# BootLoader.net
KiCad netlist of a schematic drawn in EAGLE
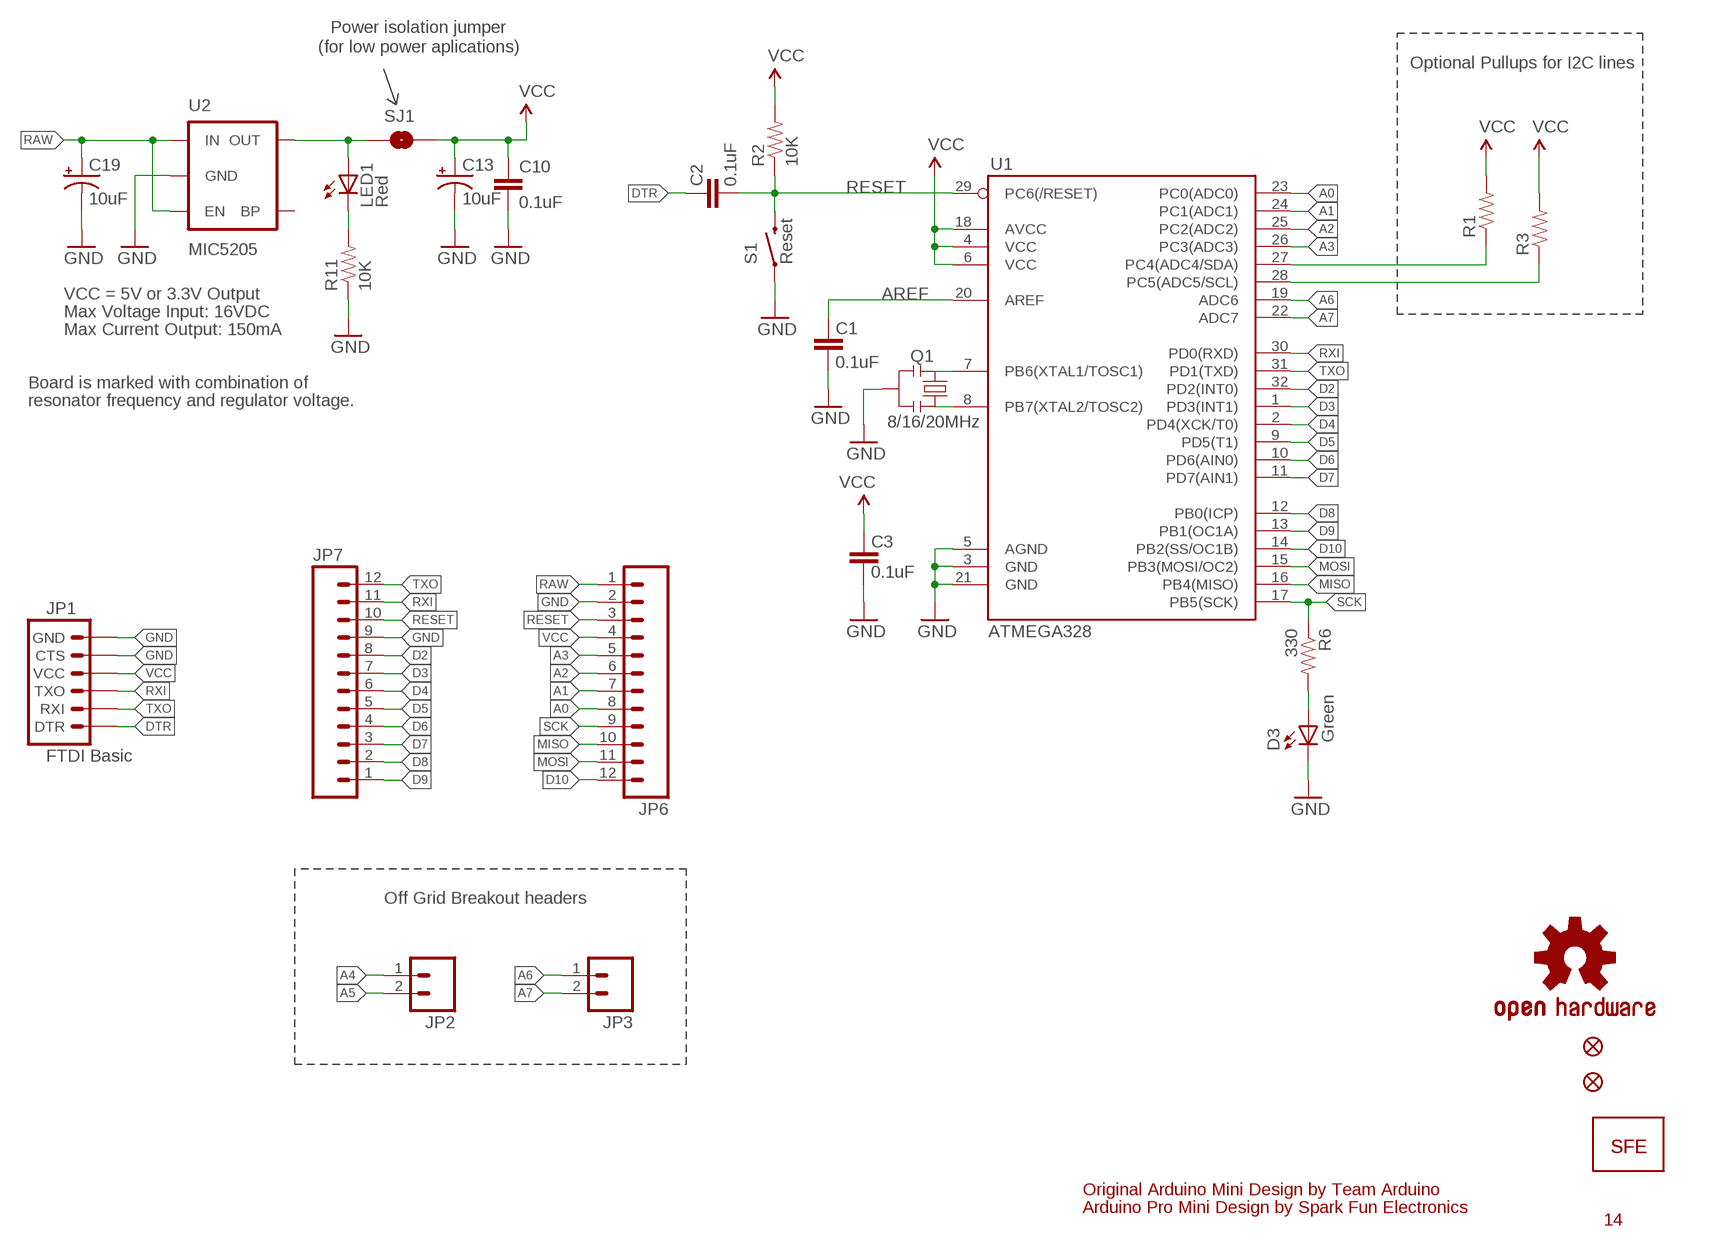
[diagram p0: schematic, sheet 1]

(export (version "E")
  (design (tool "Eeschema 10.0.6"))
  (components
    (comp (ref "C1")
      (value "0.1uF")
      (footprint "eagle-import:0603-CAP")
      (libsource (lib "eagle-import") (part "CAP0603-CAP"))
    )
    (comp (ref "C2")
      (value "0.1uF")
      (footprint "eagle-import:0603-CAP")
      (libsource (lib "eagle-import") (part "CAP0603-CAP"))
    )
    (comp (ref "C3")
      (value "0.1uF")
      (footprint "eagle-import:0603-CAP")
      (libsource (lib "eagle-import") (part "CAP0603-CAP"))
    )
    (comp (ref "C10")
      (value "0.1uF")
      (footprint "eagle-import:0603-CAP")
      (libsource (lib "eagle-import") (part "CAP0603-CAP"))
    )
    (comp (ref "C13")
      (value "10uF")
      (footprint "eagle-import:EIA3216")
      (libsource (lib "eagle-import") (part "CAP_POL1206"))
    )
    (comp (ref "C19")
      (value "10uF")
      (footprint "eagle-import:EIA3216")
      (libsource (lib "eagle-import") (part "CAP_POL1206"))
    )
    (comp (ref "D3")
      (value "Green")
      (footprint "eagle-import:0603-LED-ALT1")
      (libsource (lib "eagle-import") (part "LED"))
    )
    (comp (ref "JP1")
      (value "FTDI Basic")
      (footprint "eagle-import:1X06")
      (libsource (lib "eagle-import") (part "ARDUINO_SERIAL_PROGRAMPTH"))
    )
    (comp (ref "JP2")
      (value "M02PTH")
      (footprint "eagle-import:1X02")
      (libsource (lib "eagle-import") (part "M02PTH"))
    )
    (comp (ref "JP3")
      (value "M02PTH")
      (footprint "eagle-import:1X02")
      (libsource (lib "eagle-import") (part "M02PTH"))
    )
    (comp (ref "JP5")
      (value "FIDUCIALUFIDUCIAL")
      (footprint "eagle-import:MICRO-FIDUCIAL")
      (libsource (lib "eagle-import") (part "FIDUCIALUFIDUCIAL"))
    )
    (comp (ref "JP6")
      (value "M12PTH")
      (footprint "eagle-import:1X12")
      (libsource (lib "eagle-import") (part "M12PTH"))
    )
    (comp (ref "JP7")
      (value "M12PTH")
      (footprint "eagle-import:1X12")
      (libsource (lib "eagle-import") (part "M12PTH"))
    )
    (comp (ref "JP8")
      (value "FIDUCIALUFIDUCIAL")
      (footprint "eagle-import:MICRO-FIDUCIAL")
      (libsource (lib "eagle-import") (part "FIDUCIALUFIDUCIAL"))
    )
    (comp (ref "LED1")
      (value "Red")
      (footprint "eagle-import:0603-LED-ALT1")
      (libsource (lib "eagle-import") (part "LED"))
    )
    (comp (ref "Q1")
      (value "8/16/20MHz")
      (footprint "eagle-import:RESONATOR-SMD-1_1")
      (libsource (lib "eagle-import") (part "RESONATOR1{colon}1"))
    )
    (comp (ref "R1")
      (value "RESISTOR0603-RES")
      (footprint "eagle-import:0603-RES")
      (libsource (lib "eagle-import") (part "RESISTOR0603-RES"))
    )
    (comp (ref "R2")
      (value "10K")
      (footprint "eagle-import:0603-RES")
      (libsource (lib "eagle-import") (part "RESISTOR0603-RES"))
    )
    (comp (ref "R3")
      (value "RESISTOR0603-RES")
      (footprint "eagle-import:0603-RES")
      (libsource (lib "eagle-import") (part "RESISTOR0603-RES"))
    )
    (comp (ref "R6")
      (value "330")
      (footprint "eagle-import:0603-RES")
      (libsource (lib "eagle-import") (part "RESISTOR0603-RES"))
    )
    (comp (ref "R11")
      (value "10K")
      (footprint "eagle-import:0603-RES")
      (libsource (lib "eagle-import") (part "RESISTOR0603-RES"))
    )
    (comp (ref "S1")
      (value "Reset")
      (footprint "eagle-import:TACTILE-SWITCH-SMD-ALT01")
      (libsource (lib "eagle-import") (part "SWITCH-MOMENTARY-2SMD-ALT01"))
    )
    (comp (ref "SJ1")
      (value "SOLDERJUMPERNC")
      (footprint "eagle-import:SJ_2S")
      (libsource (lib "eagle-import") (part "SOLDERJUMPERNC"))
    )
    (comp (ref "U$1")
      (value "LOGO-SFESK")
      (footprint "eagle-import:SFE-LOGO-FLAME")
      (libsource (lib "eagle-import") (part "LOGO-SFESK"))
    )
    (comp (ref "U$3")
      (value "OSHW-LOGOS")
      (footprint "eagle-import:OSHW-LOGO-S")
      (libsource (lib "eagle-import") (part "OSHW-LOGOS"))
    )
    (comp (ref "U$11")
      (value "LOGO-SFENEW")
      (footprint "eagle-import:SFE-NEW-WEBLOGO")
      (libsource (lib "eagle-import") (part "LOGO-SFENEW"))
    )
    (comp (ref "U1")
      (value "ATMEGA328")
      (footprint "eagle-import:TQFP32-08")
      (libsource (lib "eagle-import") (part "ATMEGA168"))
    )
    (comp (ref "U2")
      (value "MIC5205")
      (footprint "eagle-import:SOT23-5")
      (libsource (lib "eagle-import") (part "V_REG_LDOSMD"))
    )
  )
  (nets
    (net (code "1") (name "/AREF") (class "Default")
      (node (ref "C1") (pin "2") (pinfunction "2_2") (pintype "passive"))
      (node (ref "U1") (pin "20") (pinfunction "AREF_20") (pintype "bidirectional"))
    )
    (net (code "2") (name "A0") (class "Default")
      (node (ref "JP6") (pin "8") (pinfunction "8_8") (pintype "passive"))
      (node (ref "U1") (pin "23") (pinfunction "PC0(ADC0)_23") (pintype "bidirectional"))
    )
    (net (code "3") (name "A1") (class "Default")
      (node (ref "JP6") (pin "7") (pinfunction "7_7") (pintype "passive"))
      (node (ref "U1") (pin "24") (pinfunction "PC1(ADC1)_24") (pintype "bidirectional"))
    )
    (net (code "4") (name "A2") (class "Default")
      (node (ref "JP6") (pin "6") (pinfunction "6_6") (pintype "passive"))
      (node (ref "U1") (pin "25") (pinfunction "PC2(ADC2)_25") (pintype "bidirectional"))
    )
    (net (code "5") (name "A3") (class "Default")
      (node (ref "JP6") (pin "5") (pinfunction "5_5") (pintype "passive"))
      (node (ref "U1") (pin "26") (pinfunction "PC3(ADC3)_26") (pintype "bidirectional"))
    )
    (net (code "6") (name "A4") (class "Default")
      (node (ref "JP2") (pin "1") (pinfunction "1_1") (pintype "passive"))
      (node (ref "R1") (pin "1") (pinfunction "1_1") (pintype "passive"))
      (node (ref "U1") (pin "27") (pinfunction "PC4(ADC4/SDA)_27") (pintype "bidirectional"))
    )
    (net (code "7") (name "A5") (class "Default")
      (node (ref "JP2") (pin "2") (pinfunction "2_2") (pintype "passive"))
      (node (ref "R3") (pin "1") (pinfunction "1_1") (pintype "passive"))
      (node (ref "U1") (pin "28") (pinfunction "PC5(ADC5/SCL)_28") (pintype "bidirectional"))
    )
    (net (code "8") (name "A6") (class "Default")
      (node (ref "JP3") (pin "1") (pinfunction "1_1") (pintype "passive"))
      (node (ref "U1") (pin "19") (pinfunction "ADC6_19") (pintype "bidirectional"))
    )
    (net (code "9") (name "A7") (class "Default")
      (node (ref "JP3") (pin "2") (pinfunction "2_2") (pintype "passive"))
      (node (ref "U1") (pin "22") (pinfunction "ADC7_22") (pintype "bidirectional"))
    )
    (net (code "10") (name "D2") (class "Default")
      (node (ref "JP7") (pin "8") (pinfunction "8_8") (pintype "passive"))
      (node (ref "U1") (pin "32") (pinfunction "PD2(INT0)_32") (pintype "bidirectional"))
    )
    (net (code "11") (name "D3") (class "Default")
      (node (ref "JP7") (pin "7") (pinfunction "7_7") (pintype "passive"))
      (node (ref "U1") (pin "1") (pinfunction "PD3(INT1)_1") (pintype "bidirectional"))
    )
    (net (code "12") (name "D4") (class "Default")
      (node (ref "JP7") (pin "6") (pinfunction "6_6") (pintype "passive"))
      (node (ref "U1") (pin "2") (pinfunction "PD4(XCK/T0)_2") (pintype "bidirectional"))
    )
    (net (code "13") (name "D5") (class "Default")
      (node (ref "JP7") (pin "5") (pinfunction "5_5") (pintype "passive"))
      (node (ref "U1") (pin "9") (pinfunction "PD5(T1)_9") (pintype "bidirectional"))
    )
    (net (code "14") (name "D6") (class "Default")
      (node (ref "JP7") (pin "4") (pinfunction "4_4") (pintype "passive"))
      (node (ref "U1") (pin "10") (pinfunction "PD6(AIN0)_10") (pintype "bidirectional"))
    )
    (net (code "15") (name "D7") (class "Default")
      (node (ref "JP7") (pin "3") (pinfunction "3_3") (pintype "passive"))
      (node (ref "U1") (pin "11") (pinfunction "PD7(AIN1)_11") (pintype "bidirectional"))
    )
    (net (code "16") (name "D8") (class "Default")
      (node (ref "JP7") (pin "2") (pinfunction "2_2") (pintype "passive"))
      (node (ref "U1") (pin "12") (pinfunction "PB0(ICP)_12") (pintype "bidirectional"))
    )
    (net (code "17") (name "D9") (class "Default")
      (node (ref "JP7") (pin "1") (pinfunction "1_1") (pintype "passive"))
      (node (ref "U1") (pin "13") (pinfunction "PB1(OC1A)_13") (pintype "bidirectional"))
    )
    (net (code "18") (name "D10") (class "Default")
      (node (ref "JP6") (pin "12") (pinfunction "12_12") (pintype "passive"))
      (node (ref "U1") (pin "14") (pinfunction "PB2(SS/OC1B)_14") (pintype "bidirectional"))
    )
    (net (code "19") (name "DTR") (class "Default")
      (node (ref "C2") (pin "2") (pinfunction "2_2") (pintype "passive"))
      (node (ref "JP1") (pin "1") (pinfunction "DTR_1") (pintype "passive"))
    )
    (net (code "20") (name "GND") (class "Default")
      (node (ref "C1") (pin "1") (pinfunction "1_1") (pintype "passive"))
      (node (ref "C10") (pin "2") (pinfunction "2_2") (pintype "passive"))
      (node (ref "C13") (pin "C") (pinfunction "-_C") (pintype "passive"))
      (node (ref "C19") (pin "C") (pinfunction "-_C") (pintype "passive"))
      (node (ref "C3") (pin "1") (pinfunction "1_1") (pintype "passive"))
      (node (ref "D3") (pin "C") (pinfunction "C_C") (pintype "passive"))
      (node (ref "JP1") (pin "5") (pinfunction "CTS_5") (pintype "passive"))
      (node (ref "JP1") (pin "6") (pinfunction "GND_6") (pintype "passive"))
      (node (ref "JP6") (pin "2") (pinfunction "2_2") (pintype "passive"))
      (node (ref "JP7") (pin "9") (pinfunction "9_9") (pintype "passive"))
      (node (ref "Q1") (pin "2") (pinfunction "2_2") (pintype "passive"))
      (node (ref "R11") (pin "1") (pinfunction "1_1") (pintype "passive"))
      (node (ref "S1") (pin "1") (pinfunction "1_1") (pintype "passive"))
      (node (ref "S1") (pin "2") (pinfunction "1_2") (pintype "passive"))
      (node (ref "U1") (pin "21") (pinfunction "GND_21") (pintype "bidirectional"))
      (node (ref "U1") (pin "3") (pinfunction "GND_3") (pintype "bidirectional"))
      (node (ref "U1") (pin "5") (pinfunction "AGND_5") (pintype "bidirectional"))
      (node (ref "U2") (pin "2") (pinfunction "GND_2") (pintype "input"))
    )
    (net (code "21") (name "MISO") (class "Default")
      (node (ref "JP6") (pin "10") (pinfunction "10_10") (pintype "passive"))
      (node (ref "U1") (pin "16") (pinfunction "PB4(MISO)_16") (pintype "bidirectional"))
    )
    (net (code "22") (name "MOSI") (class "Default")
      (node (ref "JP6") (pin "11") (pinfunction "11_11") (pintype "passive"))
      (node (ref "U1") (pin "15") (pinfunction "PB3(MOSI/OC2)_15") (pintype "bidirectional"))
    )
    (net (code "23") (name "Net-(D3-PadA)") (class "Default")
      (node (ref "D3") (pin "A") (pinfunction "A_A") (pintype "passive"))
      (node (ref "R6") (pin "2") (pinfunction "2_2") (pintype "passive"))
    )
    (net (code "24") (name "Net-(LED1-PadC)") (class "Default")
      (node (ref "LED1") (pin "C") (pinfunction "C_C") (pintype "passive"))
      (node (ref "R11") (pin "2") (pinfunction "2_2") (pintype "passive"))
    )
    (net (code "25") (name "Net-(U1-PB6(XTAL1{slash}TOSC1))") (class "Default")
      (node (ref "Q1") (pin "1") (pinfunction "1_1") (pintype "passive"))
      (node (ref "U1") (pin "7") (pinfunction "PB6(XTAL1/TOSC1)_7") (pintype "bidirectional"))
    )
    (net (code "26") (name "Net-(U1-PB7(XTAL2{slash}TOSC2))") (class "Default")
      (node (ref "Q1") (pin "3") (pinfunction "3_3") (pintype "passive"))
      (node (ref "U1") (pin "8") (pinfunction "PB7(XTAL2/TOSC2)_8") (pintype "bidirectional"))
    )
    (net (code "27") (name "Net-(U2-OUT)") (class "Default")
      (node (ref "LED1") (pin "A") (pinfunction "A_A") (pintype "passive"))
      (node (ref "SJ1") (pin "1") (pinfunction "1_1") (pintype "passive"))
      (node (ref "U2") (pin "5") (pinfunction "OUT_5") (pintype "passive"))
    )
    (net (code "28") (name "RAW") (class "Default")
      (node (ref "C19") (pin "A") (pinfunction "+_A") (pintype "passive"))
      (node (ref "JP6") (pin "1") (pinfunction "1_1") (pintype "passive"))
      (node (ref "U2") (pin "1") (pinfunction "IN_1") (pintype "input"))
      (node (ref "U2") (pin "3") (pinfunction "EN_3") (pintype "input"))
    )
    (net (code "29") (name "RESET") (class "Default")
      (node (ref "C2") (pin "1") (pinfunction "1_1") (pintype "passive"))
      (node (ref "JP6") (pin "3") (pinfunction "3_3") (pintype "passive"))
      (node (ref "JP7") (pin "10") (pinfunction "10_10") (pintype "passive"))
      (node (ref "R2") (pin "1") (pinfunction "1_1") (pintype "passive"))
      (node (ref "S1") (pin "3") (pinfunction "2_3") (pintype "passive"))
      (node (ref "S1") (pin "4") (pinfunction "2_4") (pintype "passive"))
      (node (ref "U1") (pin "29") (pinfunction "PC6(/RESET)_29") (pintype "bidirectional"))
    )
    (net (code "30") (name "RXI") (class "Default")
      (node (ref "JP1") (pin "3") (pinfunction "TXO_3") (pintype "passive"))
      (node (ref "JP7") (pin "11") (pinfunction "11_11") (pintype "passive"))
      (node (ref "U1") (pin "30") (pinfunction "PD0(RXD)_30") (pintype "bidirectional"))
    )
    (net (code "31") (name "SCK") (class "Default")
      (node (ref "JP6") (pin "9") (pinfunction "9_9") (pintype "passive"))
      (node (ref "R6") (pin "1") (pinfunction "1_1") (pintype "passive"))
      (node (ref "U1") (pin "17") (pinfunction "PB5(SCK)_17") (pintype "bidirectional"))
    )
    (net (code "32") (name "TXO") (class "Default")
      (node (ref "JP1") (pin "2") (pinfunction "RXI_2") (pintype "passive"))
      (node (ref "JP7") (pin "12") (pinfunction "12_12") (pintype "passive"))
      (node (ref "U1") (pin "31") (pinfunction "PD1(TXD)_31") (pintype "bidirectional"))
    )
    (net (code "33") (name "VCC") (class "Default")
      (node (ref "C10") (pin "1") (pinfunction "1_1") (pintype "passive"))
      (node (ref "C13") (pin "A") (pinfunction "+_A") (pintype "passive"))
      (node (ref "C3") (pin "2") (pinfunction "2_2") (pintype "passive"))
      (node (ref "JP1") (pin "4") (pinfunction "VCC_4") (pintype "passive"))
      (node (ref "JP6") (pin "4") (pinfunction "4_4") (pintype "passive"))
      (node (ref "R1") (pin "2") (pinfunction "2_2") (pintype "passive"))
      (node (ref "R2") (pin "2") (pinfunction "2_2") (pintype "passive"))
      (node (ref "R3") (pin "2") (pinfunction "2_2") (pintype "passive"))
      (node (ref "SJ1") (pin "2") (pinfunction "2_2") (pintype "passive"))
      (node (ref "U1") (pin "18") (pinfunction "AVCC_18") (pintype "bidirectional"))
      (node (ref "U1") (pin "4") (pinfunction "VCC_4") (pintype "bidirectional"))
      (node (ref "U1") (pin "6") (pinfunction "VCC_6") (pintype "bidirectional"))
    )
    (net (code "34") (name "unconnected-(U2-BP-Pad4)") (class "Default")
      (node (ref "U2") (pin "4") (pinfunction "BP_4") (pintype "input"))
    )
  )
)
